# particle_photo_relay_board.net
KiCad netlist of a schematic drawn in EAGLE
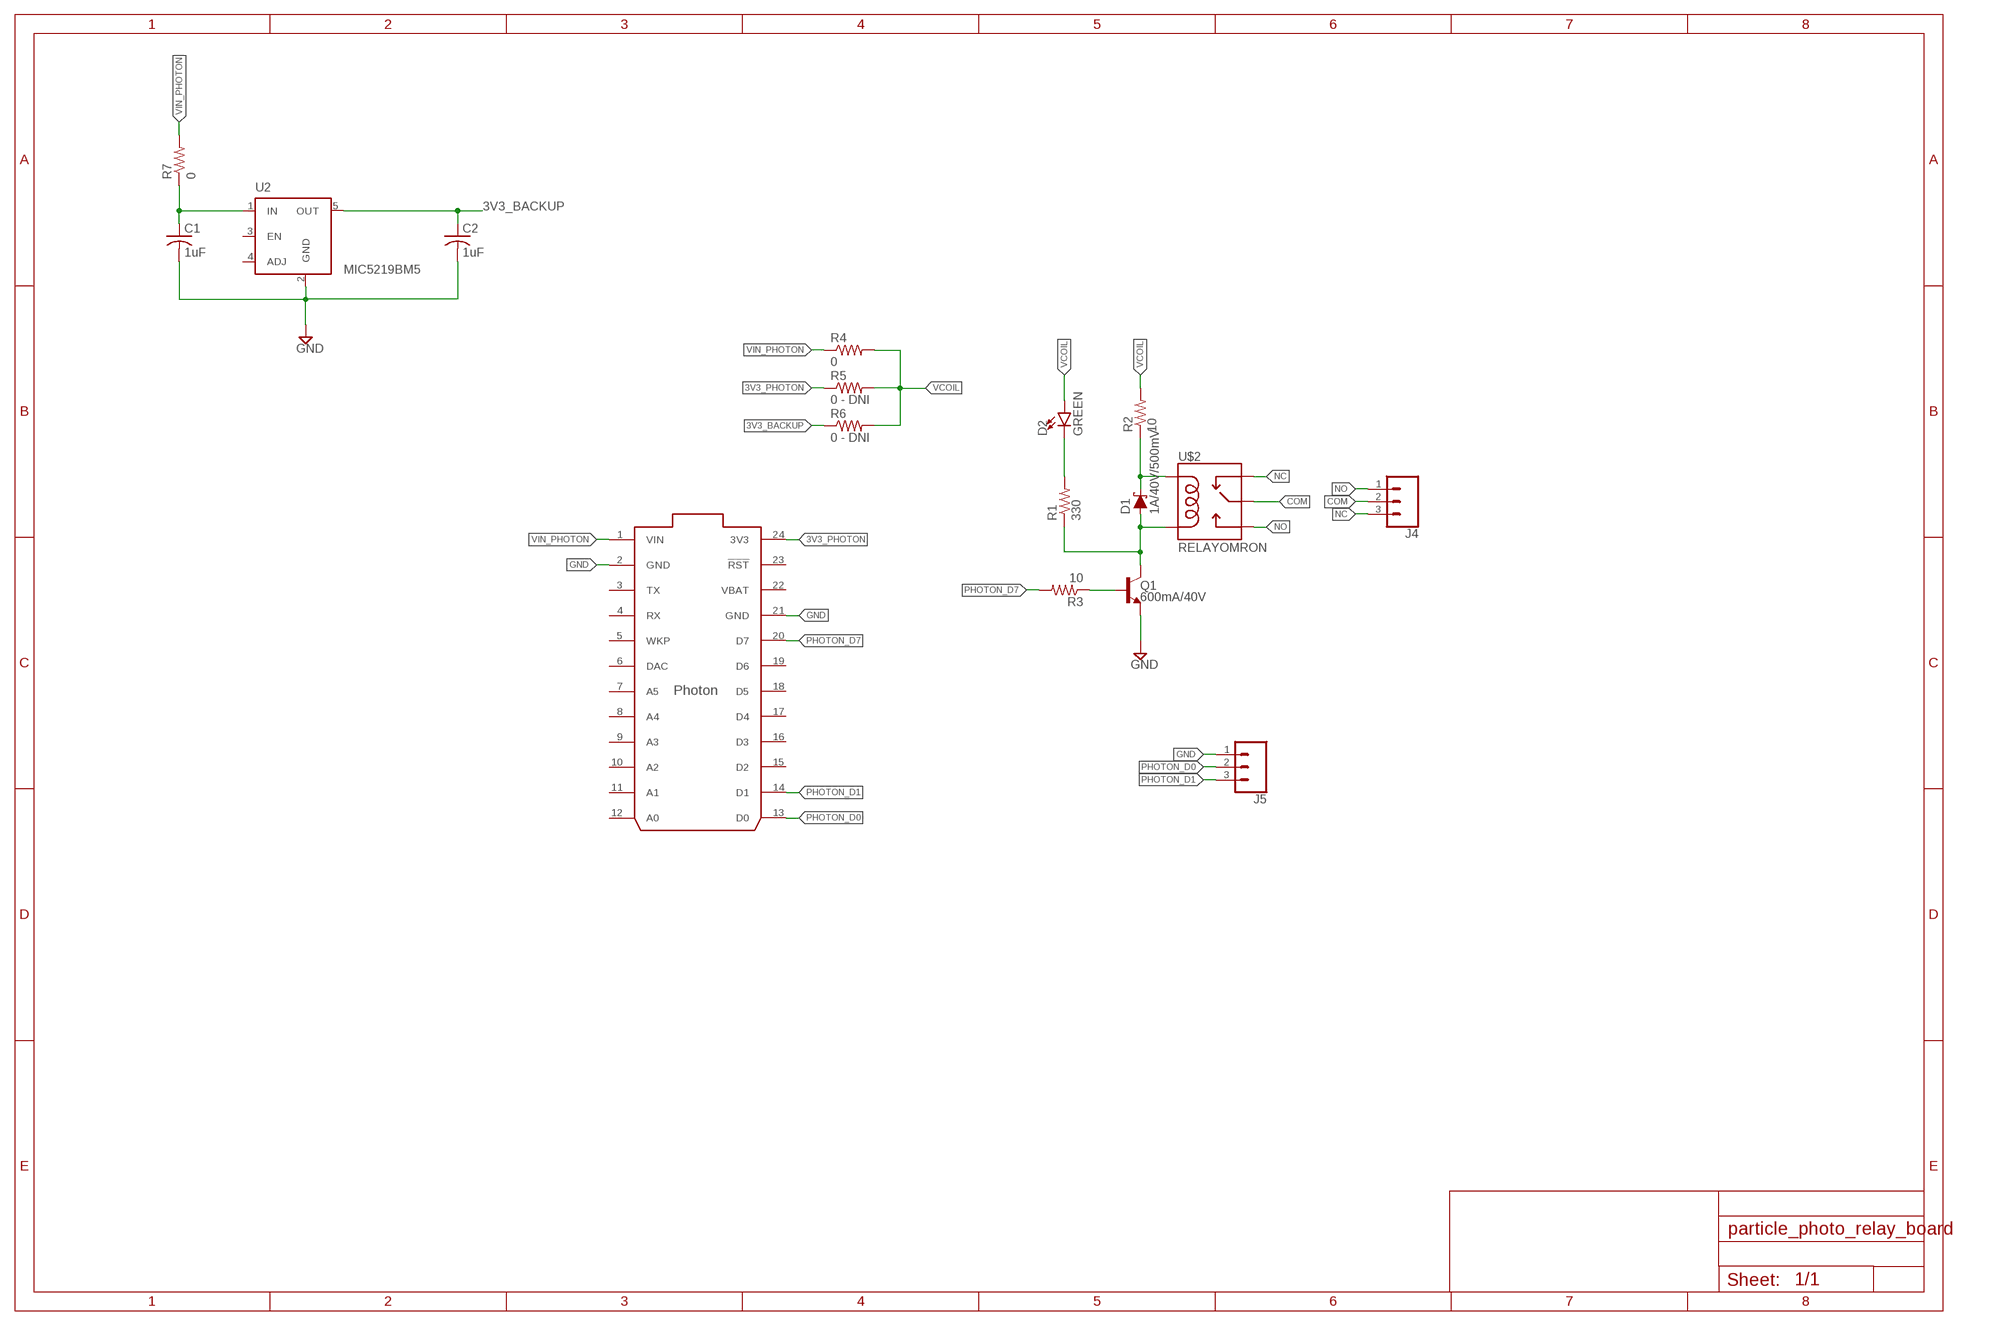
[diagram p0: schematic, sheet 1]

(export (version "E")
  (design (tool "Eeschema 10.0.6"))
  (components
    (comp (ref "C1")
      (value "1uF")
      (footprint "eagle-import:C0805")
      (libsource (lib "eagle-import") (part "C-USC0805"))
    )
    (comp (ref "C2")
      (value "1uF")
      (footprint "eagle-import:C0805")
      (libsource (lib "eagle-import") (part "C-USC0805"))
    )
    (comp (ref "D1")
      (value "1A/40V/500mV")
      (footprint "eagle-import:SMA-DIODE")
      (libsource (lib "eagle-import") (part "DIODE-SCHOTTKY-SS14"))
    )
    (comp (ref "D2")
      (value "GREEN")
      (footprint "eagle-import:LED-1206")
      (libsource (lib "eagle-import") (part "LED-GREEN1206"))
    )
    (comp (ref "J4")
      (value "CONN_03-SCREW-5MM")
      (footprint "eagle-import:SCREWTERMINAL-5MM-3")
      (libsource (lib "eagle-import") (part "CONN_03-SCREW-5MM"))
    )
    (comp (ref "J5")
      (value "CONN_03-SCREW-5MM")
      (footprint "eagle-import:SCREWTERMINAL-5MM-3")
      (libsource (lib "eagle-import") (part "CONN_03-SCREW-5MM"))
    )
    (comp (ref "Q1")
      (value "600mA/40V")
      (footprint "eagle-import:SOT23-3")
      (libsource (lib "eagle-import") (part "TRANS_NPN-MMBT2222AL"))
    )
    (comp (ref "R1")
      (value "330")
      (footprint "eagle-import:R0805")
      (libsource (lib "eagle-import") (part "R-US_R0805"))
    )
    (comp (ref "R2")
      (value "10")
      (footprint "eagle-import:R0805")
      (libsource (lib "eagle-import") (part "R-US_R0805"))
    )
    (comp (ref "R3")
      (value "10")
      (footprint "eagle-import:R0805")
      (libsource (lib "eagle-import") (part "R-US_R0805"))
    )
    (comp (ref "R4")
      (value "0")
      (footprint "eagle-import:R0805")
      (libsource (lib "eagle-import") (part "R-US_R0805"))
    )
    (comp (ref "R5")
      (value "0 - DNI")
      (footprint "eagle-import:R0805")
      (libsource (lib "eagle-import") (part "R-US_R0805"))
    )
    (comp (ref "R6")
      (value "0 - DNI")
      (footprint "eagle-import:R0805")
      (libsource (lib "eagle-import") (part "R-US_R0805"))
    )
    (comp (ref "R7")
      (value "0")
      (footprint "eagle-import:R0805")
      (libsource (lib "eagle-import") (part "R-US_R0805"))
    )
    (comp (ref "U$1")
      (value "PHOTON_WITH_HEADERS")
      (footprint "eagle-import:PHOTON")
      (libsource (lib "eagle-import") (part "PHOTON_WITH_HEADERS"))
    )
    (comp (ref "U$2")
      (value "RELAYOMRON")
      (footprint "eagle-import:G5LE-14-DC5")
      (libsource (lib "eagle-import") (part "RELAYOMRON"))
    )
    (comp (ref "U2")
      (value "MIC5219BM5")
      (footprint "eagle-import:SOT23-5")
      (fields (field (name "MF") "ALTERA CORPORATION") (field (name "MPN") "MIC5219BM5 TR"))
      (libsource (lib "eagle-import") (part "MIC5219BM5"))
    )
  )
  (nets
    (net (code "1") (name "/VBAT") (class "Default")
      (node (ref "U$1") (pin "22") (pinfunction "VBAT_22") (pintype "power_in"))
    )
    (net (code "2") (name "3V3_BACKUP") (class "Default")
      (node (ref "C2") (pin "1") (pinfunction "1_1") (pintype "passive"))
      (node (ref "R6") (pin "1") (pinfunction "1_1") (pintype "passive"))
      (node (ref "U2") (pin "5") (pinfunction "OUT_5") (pintype "output"))
    )
    (net (code "3") (name "3V3_PHOTON") (class "Default")
      (node (ref "R5") (pin "1") (pinfunction "1_1") (pintype "passive"))
      (node (ref "U$1") (pin "24") (pinfunction "3V3_24") (pintype "power_in"))
    )
    (net (code "4") (name "COM") (class "Default")
      (node (ref "J4") (pin "2") (pinfunction "2_2") (pintype "passive"))
      (node (ref "U$2") (pin "COMMON") (pinfunction "MAIN_COMMON") (pintype "bidirectional"))
    )
    (net (code "5") (name "GND") (class "Default")
      (node (ref "C1") (pin "2") (pinfunction "2_2") (pintype "passive"))
      (node (ref "C2") (pin "2") (pinfunction "2_2") (pintype "passive"))
      (node (ref "J5") (pin "1") (pinfunction "1_1") (pintype "passive"))
      (node (ref "Q1") (pin "2") (pinfunction "E_2") (pintype "passive"))
      (node (ref "U$1") (pin "2") (pinfunction "GND_2") (pintype "power_in"))
      (node (ref "U$1") (pin "21") (pinfunction "GND_21") (pintype "power_in"))
      (node (ref "U2") (pin "2") (pinfunction "GND_2") (pintype "power_in"))
    )
    (net (code "6") (name "NC") (class "Default")
      (node (ref "J4") (pin "3") (pinfunction "3_3") (pintype "passive"))
      (node (ref "U$2") (pin "CLOSED") (pinfunction "NC_CLOSED") (pintype "bidirectional"))
    )
    (net (code "7") (name "NO") (class "Default")
      (node (ref "J4") (pin "1") (pinfunction "1_1") (pintype "passive"))
      (node (ref "U$2") (pin "OPEN") (pinfunction "NO_OPEN") (pintype "bidirectional"))
    )
    (net (code "8") (name "Net-(D1-PadC)") (class "Default")
      (node (ref "D1") (pin "C") (pinfunction "C_C") (pintype "passive"))
      (node (ref "R2") (pin "1") (pinfunction "1_1") (pintype "passive"))
      (node (ref "U$2") (pin "COIL1") (pinfunction "COIL1_COIL1") (pintype "bidirectional"))
    )
    (net (code "9") (name "Net-(D2-PadC)") (class "Default")
      (node (ref "D2") (pin "C") (pinfunction "C_C") (pintype "passive"))
      (node (ref "R1") (pin "2") (pinfunction "2_2") (pintype "passive"))
    )
    (net (code "10") (name "Net-(Q1-B)") (class "Default")
      (node (ref "Q1") (pin "1") (pinfunction "B_1") (pintype "passive"))
      (node (ref "R3") (pin "1") (pinfunction "1_1") (pintype "passive"))
    )
    (net (code "11") (name "Net-(Q1-C)") (class "Default")
      (node (ref "D1") (pin "A") (pinfunction "A_A") (pintype "passive"))
      (node (ref "Q1") (pin "3") (pinfunction "C_3") (pintype "passive"))
      (node (ref "R1") (pin "1") (pinfunction "1_1") (pintype "passive"))
      (node (ref "U$2") (pin "COIL2") (pinfunction "COIL2_COIL2") (pintype "bidirectional"))
    )
    (net (code "12") (name "Net-(U2-IN)") (class "Default")
      (node (ref "C1") (pin "1") (pinfunction "1_1") (pintype "passive"))
      (node (ref "R7") (pin "1") (pinfunction "1_1") (pintype "passive"))
      (node (ref "U2") (pin "1") (pinfunction "IN_1") (pintype "input"))
    )
    (net (code "13") (name "PHOTON_D0") (class "Default")
      (node (ref "J5") (pin "2") (pinfunction "2_2") (pintype "passive"))
      (node (ref "U$1") (pin "13") (pinfunction "D0_13") (pintype "bidirectional"))
    )
    (net (code "14") (name "PHOTON_D1") (class "Default")
      (node (ref "J5") (pin "3") (pinfunction "3_3") (pintype "passive"))
      (node (ref "U$1") (pin "14") (pinfunction "D1_14") (pintype "bidirectional"))
    )
    (net (code "15") (name "PHOTON_D7") (class "Default")
      (node (ref "R3") (pin "2") (pinfunction "2_2") (pintype "passive"))
      (node (ref "U$1") (pin "20") (pinfunction "D7_20") (pintype "bidirectional"))
    )
    (net (code "16") (name "VCOIL") (class "Default")
      (node (ref "D2") (pin "A") (pinfunction "A_A") (pintype "passive"))
      (node (ref "R2") (pin "2") (pinfunction "2_2") (pintype "passive"))
      (node (ref "R4") (pin "2") (pinfunction "2_2") (pintype "passive"))
      (node (ref "R5") (pin "2") (pinfunction "2_2") (pintype "passive"))
      (node (ref "R6") (pin "2") (pinfunction "2_2") (pintype "passive"))
    )
    (net (code "17") (name "VIN_PHOTON") (class "Default")
      (node (ref "R4") (pin "1") (pinfunction "1_1") (pintype "passive"))
      (node (ref "R7") (pin "2") (pinfunction "2_2") (pintype "passive"))
      (node (ref "U$1") (pin "1") (pinfunction "VIN_1") (pintype "power_in"))
    )
    (net (code "18") (name "unconnected-(U$1-A0-Pad12)") (class "Default")
      (node (ref "U$1") (pin "12") (pinfunction "A0_12") (pintype "bidirectional"))
    )
    (net (code "19") (name "unconnected-(U$1-A1-Pad11)") (class "Default")
      (node (ref "U$1") (pin "11") (pinfunction "A1_11") (pintype "bidirectional"))
    )
    (net (code "20") (name "unconnected-(U$1-A2-Pad10)") (class "Default")
      (node (ref "U$1") (pin "10") (pinfunction "A2_10") (pintype "bidirectional"))
    )
    (net (code "21") (name "unconnected-(U$1-A3-Pad9)") (class "Default")
      (node (ref "U$1") (pin "9") (pinfunction "A3_9") (pintype "bidirectional"))
    )
    (net (code "22") (name "unconnected-(U$1-A4-Pad8)") (class "Default")
      (node (ref "U$1") (pin "8") (pinfunction "A4_8") (pintype "bidirectional"))
    )
    (net (code "23") (name "unconnected-(U$1-A5-Pad7)") (class "Default")
      (node (ref "U$1") (pin "7") (pinfunction "A5_7") (pintype "bidirectional"))
    )
    (net (code "24") (name "unconnected-(U$1-D2-Pad15)") (class "Default")
      (node (ref "U$1") (pin "15") (pinfunction "D2_15") (pintype "bidirectional"))
    )
    (net (code "25") (name "unconnected-(U$1-D3-Pad16)") (class "Default")
      (node (ref "U$1") (pin "16") (pinfunction "D3_16") (pintype "bidirectional"))
    )
    (net (code "26") (name "unconnected-(U$1-D4-Pad17)") (class "Default")
      (node (ref "U$1") (pin "17") (pinfunction "D4_17") (pintype "bidirectional"))
    )
    (net (code "27") (name "unconnected-(U$1-D5-Pad18)") (class "Default")
      (node (ref "U$1") (pin "18") (pinfunction "D5_18") (pintype "bidirectional"))
    )
    (net (code "28") (name "unconnected-(U$1-D6-Pad19)") (class "Default")
      (node (ref "U$1") (pin "19") (pinfunction "D6_19") (pintype "bidirectional"))
    )
    (net (code "29") (name "unconnected-(U$1-DAC-Pad6)") (class "Default")
      (node (ref "U$1") (pin "6") (pinfunction "DAC_6") (pintype "bidirectional"))
    )
    (net (code "30") (name "unconnected-(U$1-RX-Pad4)") (class "Default")
      (node (ref "U$1") (pin "4") (pinfunction "RX_4") (pintype "bidirectional"))
    )
    (net (code "31") (name "unconnected-(U$1-TX-Pad3)") (class "Default")
      (node (ref "U$1") (pin "3") (pinfunction "TX_3") (pintype "bidirectional"))
    )
    (net (code "32") (name "unconnected-(U$1-WKP-Pad5)") (class "Default")
      (node (ref "U$1") (pin "5") (pinfunction "WKP_5") (pintype "bidirectional"))
    )
    (net (code "33") (name "unconnected-(U$1-~{RST}-Pad23)") (class "Default")
      (node (ref "U$1") (pin "23") (pinfunction "~{RST}_23") (pintype "bidirectional"))
    )
    (net (code "34") (name "unconnected-(U2-ADJ-Pad4)") (class "Default")
      (node (ref "U2") (pin "4") (pinfunction "ADJ_4") (pintype "passive"))
    )
    (net (code "35") (name "unconnected-(U2-EN-Pad3)") (class "Default")
      (node (ref "U2") (pin "3") (pinfunction "EN_3") (pintype "input"))
    )
  )
)
